# SSR.net
KiCad netlist of a schematic drawn in Altium Designer
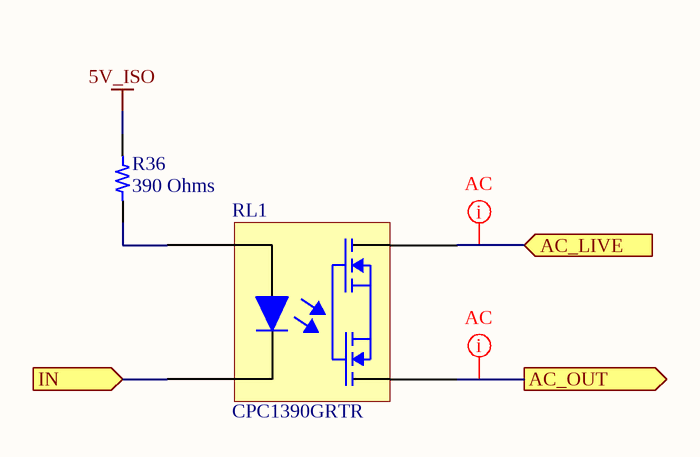
[diagram p0: SSR.SchDoc]

(export (version "E")
  (design (tool "Eeschema 10.0.6"))
  (components
    (comp (ref "R36")
      (value "390 Ohms")
      (footprint "RES 0603_1608")
      (description "RES 390 OHM 1% 1/10W 0603")
      (fields (field (name "PART NUMBER") "CRCW0603390RFKEAC") (field (name "MANUFACTURER") "Vishay Dale"))
      (libsource (lib "altiumlibrary.com") (part "Resistor"))
    )
    (comp (ref "RL1")
      (value "CPC1390GRTR")
      (footprint "IXYS SOP-4 CPC1390GR")
      (description "SSR RELAY SPST-NO 140MA 0-400V")
      (fields (field (name "MANUFACTURER") "IXYS Integrated Circuits Division"))
      (libsource (lib "altiumlibrary.com") (part "IXYS CPC1390"))
    )
  )
  (nets
    (net (code "1") (name "/AC_LIVE") (class "Default")
      (node (ref "RL1") (pin "4") (pinfunction "4_4") (pintype "passive"))
    )
    (net (code "2") (name "/AC_OUT") (class "Default")
      (node (ref "RL1") (pin "3") (pinfunction "3_3") (pintype "passive"))
    )
    (net (code "3") (name "/IN") (class "Default")
      (node (ref "RL1") (pin "2") (pinfunction "2_2") (pintype "passive"))
    )
    (net (code "4") (name "5V_ISO") (class "Default")
      (node (ref "R36") (pin "2") (pinfunction "2_2") (pintype "passive"))
    )
    (net (code "5") (name "Net-(R36-Pad1)") (class "Default")
      (node (ref "R36") (pin "1") (pinfunction "1_1") (pintype "passive"))
      (node (ref "RL1") (pin "1") (pinfunction "1_1") (pintype "passive"))
    )
  )
)
